# Grove_-_LED_Strip_driver_V1_2.net
KiCad netlist of a schematic drawn in EAGLE
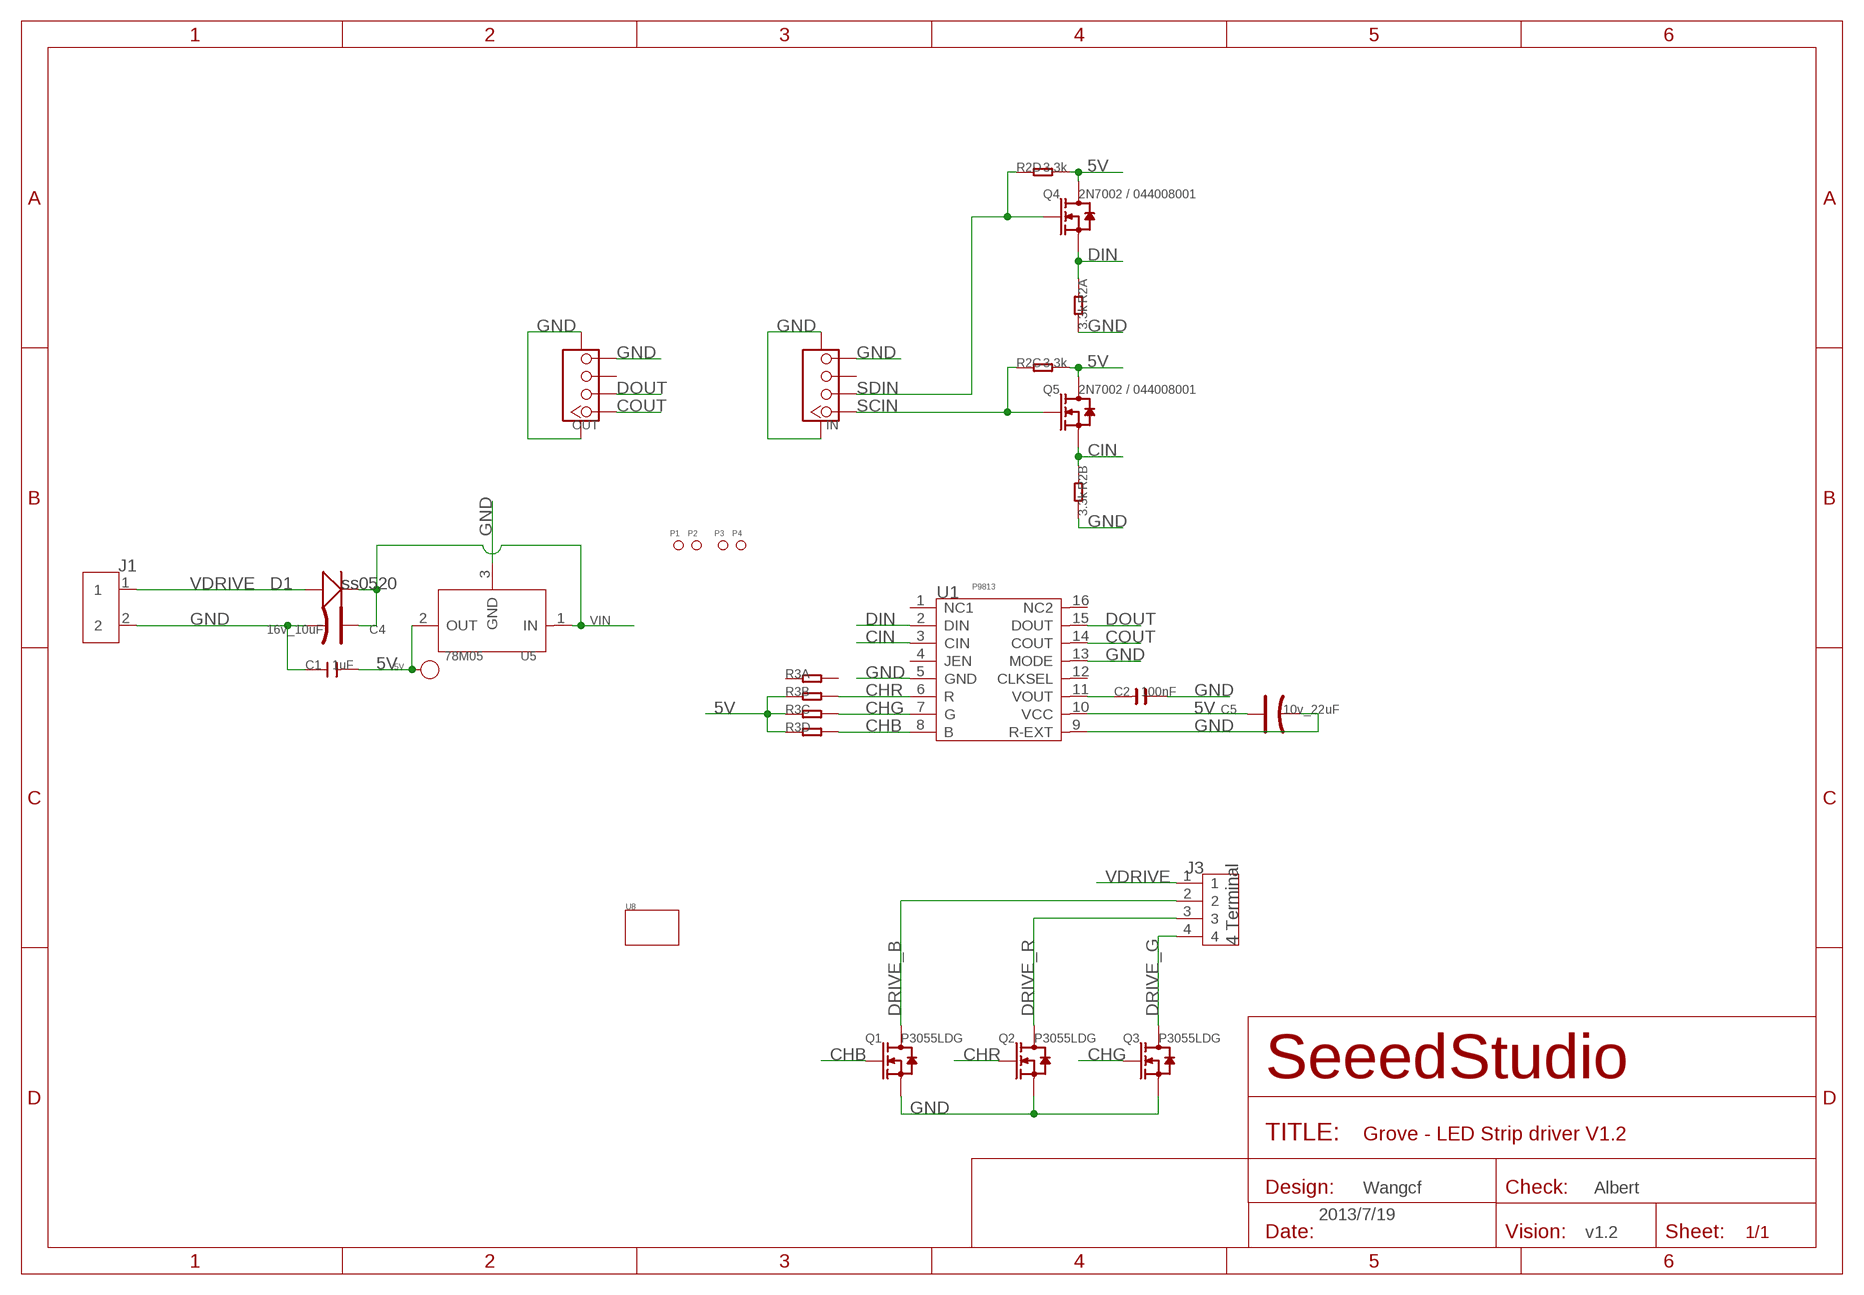
[diagram p0: schematic, sheet 1]

(export (version "E")
  (design (tool "Eeschema 10.0.6"))
  (components
    (comp (ref "5V")
      (value "DNP")
      (footprint "eagle-import:TP_3535")
      (libsource (lib "eagle-import") (part "PAD-TEST-POINT'3535'"))
    )
    (comp (ref "C1")
      (value "1uF")
      (footprint "eagle-import:C0805")
      (libsource (lib "eagle-import") (part "C-0805"))
    )
    (comp (ref "C2")
      (value "100nF")
      (footprint "eagle-import:C0603")
      (libsource (lib "eagle-import") (part "OPL_C-0603"))
    )
    (comp (ref "C4")
      (value "16v_10uF")
      (footprint "eagle-import:AVX-A")
      (libsource (lib "eagle-import") (part "CAP-AVX-A"))
    )
    (comp (ref "C5")
      (value "10v_22uF")
      (footprint "eagle-import:AVX-A")
      (libsource (lib "eagle-import") (part "CAP-AVX-A"))
    )
    (comp (ref "D1")
      (value "ss0520")
      (footprint "eagle-import:SOD123")
      (libsource (lib "eagle-import") (part "D'1206'"))
    )
    (comp (ref "IN")
      (value "TWIG-4P-2.0-SMD-FEMALE-REINFORCE'DD'")
      (footprint "eagle-import:4P-SMD-2.0")
      (libsource (lib "eagle-import") (part "TWIG-4P-2.0-SMD-FEMALE-REINFORCE'DD'"))
    )
    (comp (ref "J1")
      (value "SCREW-TERMINAL-2P'3.5'")
      (footprint "eagle-import:2P-3.5")
      (libsource (lib "eagle-import") (part "SCREW-TERMINAL-2P'3.5'"))
    )
    (comp (ref "J3")
      (value "4 Terminal")
      (footprint "eagle-import:4P-3.5")
      (libsource (lib "eagle-import") (part "SCREW-TERMINAL-4P'3.5'"))
    )
    (comp (ref "OUT")
      (value "TWIG-4P-2.0-SMD-FEMALE-REINFORCE'DD'")
      (footprint "eagle-import:4P-SMD-2.0")
      (libsource (lib "eagle-import") (part "TWIG-4P-2.0-SMD-FEMALE-REINFORCE'DD'"))
    )
    (comp (ref "P1")
      (value "PAD-MARK")
      (footprint "eagle-import:ROUND-MARK-1.0")
      (fields (field (name "PARTNO") "DNP"))
      (libsource (lib "eagle-import") (part "PAD-MARK"))
    )
    (comp (ref "P2")
      (value "PAD-MARK")
      (footprint "eagle-import:ROUND-MARK-1.0")
      (fields (field (name "PARTNO") "DNP"))
      (libsource (lib "eagle-import") (part "PAD-MARK"))
    )
    (comp (ref "P3")
      (value "PAD-MARK")
      (footprint "eagle-import:ROUND-MARK-1.0")
      (fields (field (name "PARTNO") "DNP"))
      (libsource (lib "eagle-import") (part "PAD-MARK"))
    )
    (comp (ref "P4")
      (value "PAD-MARK")
      (footprint "eagle-import:ROUND-MARK-1.0")
      (fields (field (name "PARTNO") "DNP"))
      (libsource (lib "eagle-import") (part "PAD-MARK"))
    )
    (comp (ref "Q1")
      (value "P3055LDG")
      (footprint "eagle-import:TO252")
      (libsource (lib "eagle-import") (part "MOSFET-N'P3055LDG'"))
    )
    (comp (ref "Q2")
      (value "P3055LDG")
      (footprint "eagle-import:TO252")
      (libsource (lib "eagle-import") (part "MOSFET-N'P3055LDG'"))
    )
    (comp (ref "Q3")
      (value "P3055LDG")
      (footprint "eagle-import:TO252")
      (libsource (lib "eagle-import") (part "MOSFET-N'P3055LDG'"))
    )
    (comp (ref "Q4")
      (value "2N7002 / 044008001")
      (footprint "eagle-import:SOT23")
      (libsource (lib "eagle-import") (part "MOSFET-N'SOT23'"))
    )
    (comp (ref "Q5")
      (value "2N7002 / 044008001")
      (footprint "eagle-import:SOT23")
      (libsource (lib "eagle-import") (part "MOSFET-N'SOT23'"))
    )
    (comp (ref "R2")
      (value "3.3k")
      (footprint "eagle-import:R1206-8")
      (libsource (lib "eagle-import") (part "R-4R"))
    )
    (comp (ref "R3")
      (value "R-4R-1206")
      (footprint "eagle-import:1206-8-3.3X2.4")
      (libsource (lib "eagle-import") (part "R-4R-1206"))
    )
    (comp (ref "U1")
      (value "P9813")
      (footprint "eagle-import:SSOP16")
      (libsource (lib "eagle-import") (part "P9813-SSOP16"))
    )
    (comp (ref "U5")
      (value "78M05")
      (footprint "eagle-import:TO252")
      (libsource (lib "eagle-import") (part "78M05-TO252"))
    )
    (comp (ref "U8")
      (value "TWIG'3U'")
      (footprint "eagle-import:3U-DIM-W_-DRILL")
      (libsource (lib "eagle-import") (part "TWIG'3U'"))
    )
  )
  (nets
    (net (code "1") (name "/5V") (class "Default")
      (node (ref "5V") (pin "T") (pinfunction "T_T") (pintype "bidirectional"))
      (node (ref "C1") (pin "2") (pinfunction "2_2") (pintype "passive"))
      (node (ref "C5") (pin "+") (pinfunction "+_+") (pintype "passive"))
      (node (ref "Q4") (pin "3") (pinfunction "D_3") (pintype "passive"))
      (node (ref "Q5") (pin "3") (pinfunction "D_3") (pintype "passive"))
      (node (ref "R2") (pin "5") (pinfunction "2_5") (pintype "passive"))
      (node (ref "R2") (pin "6") (pinfunction "2_6") (pintype "passive"))
      (node (ref "R3") (pin "2") (pinfunction "1_2") (pintype "passive"))
      (node (ref "R3") (pin "3") (pinfunction "1_3") (pintype "passive"))
      (node (ref "R3") (pin "4") (pinfunction "1_4") (pintype "passive"))
      (node (ref "U1") (pin "10") (pinfunction "VCC_10") (pintype "power_in"))
      (node (ref "U5") (pin "2") (pinfunction "OUT_2") (pintype "bidirectional"))
    )
    (net (code "2") (name "/CHB") (class "Default")
      (node (ref "Q1") (pin "1") (pinfunction "G_1") (pintype "passive"))
      (node (ref "R3") (pin "5") (pinfunction "2_5") (pintype "passive"))
      (node (ref "U1") (pin "8") (pinfunction "B_8") (pintype "output"))
    )
    (net (code "3") (name "/CHG") (class "Default")
      (node (ref "Q3") (pin "1") (pinfunction "G_1") (pintype "passive"))
      (node (ref "R3") (pin "6") (pinfunction "2_6") (pintype "passive"))
      (node (ref "U1") (pin "7") (pinfunction "G_7") (pintype "output"))
    )
    (net (code "4") (name "/CHR") (class "Default")
      (node (ref "Q2") (pin "1") (pinfunction "G_1") (pintype "passive"))
      (node (ref "R3") (pin "7") (pinfunction "2_7") (pintype "passive"))
      (node (ref "U1") (pin "6") (pinfunction "R_6") (pintype "output"))
    )
    (net (code "5") (name "/CIN") (class "Default")
      (node (ref "Q5") (pin "2") (pinfunction "S_2") (pintype "passive"))
      (node (ref "R2") (pin "2") (pinfunction "1_2") (pintype "passive"))
      (node (ref "U1") (pin "3") (pinfunction "CIN_3") (pintype "input"))
    )
    (net (code "6") (name "/COUT") (class "Default")
      (node (ref "OUT") (pin "1") (pinfunction "1_1") (pintype "bidirectional"))
      (node (ref "U1") (pin "14") (pinfunction "COUT_14") (pintype "output"))
    )
    (net (code "7") (name "/DIN") (class "Default")
      (node (ref "Q4") (pin "2") (pinfunction "S_2") (pintype "passive"))
      (node (ref "R2") (pin "1") (pinfunction "1_1") (pintype "passive"))
      (node (ref "U1") (pin "2") (pinfunction "DIN_2") (pintype "input"))
    )
    (net (code "8") (name "/DOUT") (class "Default")
      (node (ref "OUT") (pin "2") (pinfunction "2_2") (pintype "bidirectional"))
      (node (ref "U1") (pin "15") (pinfunction "DOUT_15") (pintype "output"))
    )
    (net (code "9") (name "/DRIVE_B") (class "Default")
      (node (ref "J3") (pin "2") (pinfunction "2_2") (pintype "bidirectional"))
      (node (ref "Q1") (pin "2") (pinfunction "D_2") (pintype "passive"))
    )
    (net (code "10") (name "/DRIVE_G") (class "Default")
      (node (ref "J3") (pin "4") (pinfunction "4_4") (pintype "bidirectional"))
      (node (ref "Q3") (pin "2") (pinfunction "D_2") (pintype "passive"))
    )
    (net (code "11") (name "/DRIVE_R") (class "Default")
      (node (ref "J3") (pin "3") (pinfunction "3_3") (pintype "bidirectional"))
      (node (ref "Q2") (pin "2") (pinfunction "D_2") (pintype "passive"))
    )
    (net (code "12") (name "/GND") (class "Default")
      (node (ref "C1") (pin "1") (pinfunction "1_1") (pintype "passive"))
      (node (ref "C2") (pin "2") (pinfunction "2_2") (pintype "bidirectional"))
      (node (ref "C4") (pin "-") (pinfunction "-_-") (pintype "passive"))
      (node (ref "C5") (pin "-") (pinfunction "-_-") (pintype "passive"))
      (node (ref "IN") (pin "4") (pinfunction "4_4") (pintype "bidirectional"))
      (node (ref "IN") (pin "SS1") (pinfunction "SS1_SS1") (pintype "bidirectional"))
      (node (ref "IN") (pin "SS2") (pinfunction "SS2_SS2") (pintype "bidirectional"))
      (node (ref "J1") (pin "2") (pinfunction "2_2") (pintype "bidirectional"))
      (node (ref "OUT") (pin "4") (pinfunction "4_4") (pintype "bidirectional"))
      (node (ref "OUT") (pin "SS1") (pinfunction "SS1_SS1") (pintype "bidirectional"))
      (node (ref "OUT") (pin "SS2") (pinfunction "SS2_SS2") (pintype "bidirectional"))
      (node (ref "Q1") (pin "3") (pinfunction "S_3") (pintype "passive"))
      (node (ref "Q2") (pin "3") (pinfunction "S_3") (pintype "passive"))
      (node (ref "Q3") (pin "3") (pinfunction "S_3") (pintype "passive"))
      (node (ref "R2") (pin "7") (pinfunction "2_7") (pintype "passive"))
      (node (ref "R2") (pin "8") (pinfunction "2_8") (pintype "passive"))
      (node (ref "U1") (pin "13") (pinfunction "MODE_13") (pintype "input"))
      (node (ref "U1") (pin "5") (pinfunction "GND_5") (pintype "power_in"))
      (node (ref "U1") (pin "9") (pinfunction "R-EXT_9") (pintype "input"))
      (node (ref "U5") (pin "3") (pinfunction "GND_3") (pintype "bidirectional"))
    )
    (net (code "13") (name "/SCIN") (class "Default")
      (node (ref "IN") (pin "1") (pinfunction "1_1") (pintype "bidirectional"))
      (node (ref "Q5") (pin "1") (pinfunction "G_1") (pintype "passive"))
      (node (ref "R2") (pin "3") (pinfunction "1_3") (pintype "passive"))
    )
    (net (code "14") (name "/SDIN") (class "Default")
      (node (ref "IN") (pin "2") (pinfunction "2_2") (pintype "bidirectional"))
      (node (ref "Q4") (pin "1") (pinfunction "G_1") (pintype "passive"))
      (node (ref "R2") (pin "4") (pinfunction "1_4") (pintype "passive"))
    )
    (net (code "15") (name "/VDRIVE") (class "Default")
      (node (ref "D1") (pin "+") (pinfunction "+_+") (pintype "passive"))
      (node (ref "J1") (pin "1") (pinfunction "1_1") (pintype "bidirectional"))
      (node (ref "J3") (pin "1") (pinfunction "1_1") (pintype "bidirectional"))
    )
    (net (code "16") (name "/VIN") (class "Default")
      (node (ref "C4") (pin "+") (pinfunction "+_+") (pintype "passive"))
      (node (ref "D1") (pin "-") (pinfunction "-_-") (pintype "passive"))
      (node (ref "U5") (pin "1") (pinfunction "IN_1") (pintype "bidirectional"))
    )
    (net (code "17") (name "Net-(U1-VOUT)") (class "Default")
      (node (ref "C2") (pin "1") (pinfunction "1_1") (pintype "bidirectional"))
      (node (ref "U1") (pin "11") (pinfunction "VOUT_11") (pintype "output"))
    )
    (net (code "18") (name "unconnected-(IN-Pad3)") (class "Default")
      (node (ref "IN") (pin "3") (pinfunction "3_3") (pintype "bidirectional"))
    )
    (net (code "19") (name "unconnected-(OUT-Pad3)") (class "Default")
      (node (ref "OUT") (pin "3") (pinfunction "3_3") (pintype "bidirectional"))
    )
    (net (code "20") (name "unconnected-(R3-Pad1)") (class "Default")
      (node (ref "R3") (pin "1") (pinfunction "1_1") (pintype "passive"))
    )
    (net (code "21") (name "unconnected-(R3A-2-Pad8)") (class "Default")
      (node (ref "R3") (pin "8") (pinfunction "2_8") (pintype "passive"))
    )
    (net (code "22") (name "unconnected-(U1-CLKSEL-Pad12)") (class "Default")
      (node (ref "U1") (pin "12") (pinfunction "CLKSEL_12") (pintype "input"))
    )
    (net (code "23") (name "unconnected-(U1-JEN-Pad4)") (class "Default")
      (node (ref "U1") (pin "4") (pinfunction "JEN_4") (pintype "input"))
    )
    (net (code "24") (name "unconnected-(U1-NC1-Pad1)") (class "Default")
      (node (ref "U1") (pin "1") (pinfunction "NC1_1") (pintype "no_connect"))
    )
    (net (code "25") (name "unconnected-(U1-NC2-Pad16)") (class "Default")
      (node (ref "U1") (pin "16") (pinfunction "NC2_16") (pintype "no_connect"))
    )
  )
)
